# cigar_mic.net
KiCad netlist of a schematic drawn in EAGLE
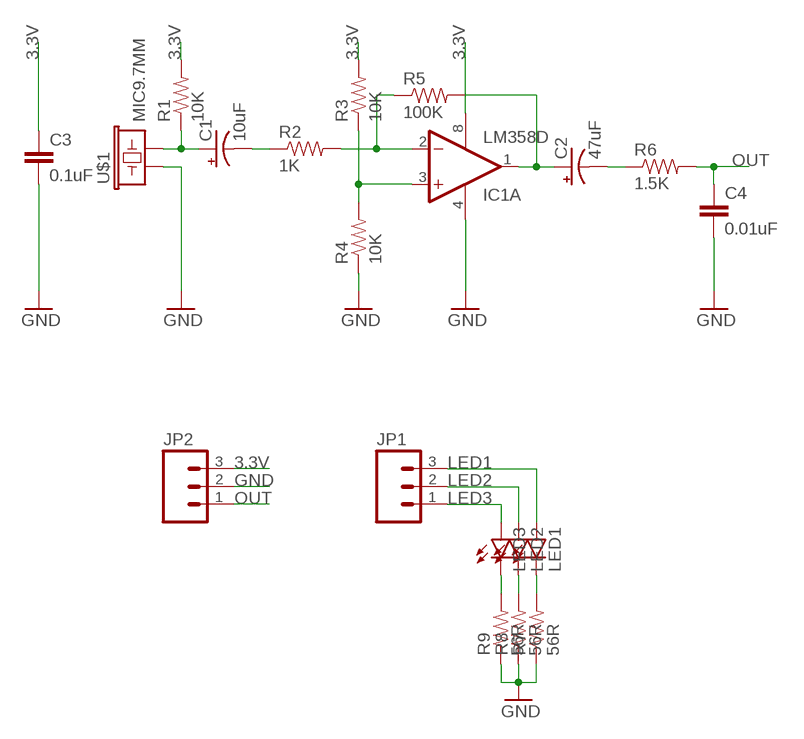
[diagram p0: schematic, sheet 1]

(export (version "E")
  (design (tool "Eeschema 10.0.6"))
  (components
    (comp (ref "C1")
      (value "10uF")
      (footprint "eagle-import:POLAR")
      (libsource (lib "eagle-import") (part "SURFACEMTPOLAR"))
    )
    (comp (ref "C2")
      (value "47uF")
      (footprint "eagle-import:POLAR")
      (libsource (lib "eagle-import") (part "SURFACEMTPOLAR"))
    )
    (comp (ref "C3")
      (value "0.1uF")
      (footprint "eagle-import:0805")
      (libsource (lib "eagle-import") (part "CAP0805"))
    )
    (comp (ref "C4")
      (value "0.01uF")
      (footprint "eagle-import:0805")
      (libsource (lib "eagle-import") (part "CAP0805"))
    )
    (comp (ref "IC1")
      (value "LM358D")
      (footprint "eagle-import:SO08")
      (libsource (lib "eagle-import") (part "LM358D"))
    )
    (comp (ref "JP1")
      (value "M031X03_NO_SILK")
      (footprint "eagle-import:1X03_NO_SILK")
      (libsource (lib "eagle-import") (part "M031X03_NO_SILK"))
    )
    (comp (ref "JP2")
      (value "M031X03_NO_SILK")
      (footprint "eagle-import:1X03_NO_SILK")
      (libsource (lib "eagle-import") (part "M031X03_NO_SILK"))
    )
    (comp (ref "LED1")
      (value "LED0603")
      (footprint "eagle-import:LED-0603")
      (libsource (lib "eagle-import") (part "LED0603"))
    )
    (comp (ref "LED2")
      (value "LED0603")
      (footprint "eagle-import:LED-0603")
      (libsource (lib "eagle-import") (part "LED0603"))
    )
    (comp (ref "LED3")
      (value "LED0603")
      (footprint "eagle-import:LED-0603")
      (libsource (lib "eagle-import") (part "LED0603"))
    )
    (comp (ref "R1")
      (value "10K")
      (footprint "eagle-import:0603-RES")
      (libsource (lib "eagle-import") (part "RESISTOR0603"))
    )
    (comp (ref "R2")
      (value "1K")
      (footprint "eagle-import:0603-RES")
      (libsource (lib "eagle-import") (part "RESISTOR0603"))
    )
    (comp (ref "R3")
      (value "10K")
      (footprint "eagle-import:0603-RES")
      (libsource (lib "eagle-import") (part "RESISTOR0603"))
    )
    (comp (ref "R4")
      (value "10K")
      (footprint "eagle-import:0603-RES")
      (libsource (lib "eagle-import") (part "RESISTOR0603"))
    )
    (comp (ref "R5")
      (value "100K")
      (footprint "eagle-import:0603-RES")
      (libsource (lib "eagle-import") (part "RESISTOR0603"))
    )
    (comp (ref "R6")
      (value "1.5K")
      (footprint "eagle-import:0603-RES")
      (libsource (lib "eagle-import") (part "RESISTOR0603"))
    )
    (comp (ref "R7")
      (value "56R")
      (footprint "eagle-import:0603-RES")
      (libsource (lib "eagle-import") (part "RESISTOR0603"))
    )
    (comp (ref "R8")
      (value "56R")
      (footprint "eagle-import:0603-RES")
      (libsource (lib "eagle-import") (part "RESISTOR0603"))
    )
    (comp (ref "R9")
      (value "56R")
      (footprint "eagle-import:0603-RES")
      (libsource (lib "eagle-import") (part "RESISTOR0603"))
    )
    (comp (ref "U$1")
      (value "MIC9.7MM")
      (footprint "eagle-import:MIC-9.7MM")
      (libsource (lib "eagle-import") (part "MIC9.7MM"))
    )
  )
  (nets
    (net (code "1") (name "/3.3V") (class "Default")
      (node (ref "C3") (pin "1") (pinfunction "1_1") (pintype "passive"))
      (node (ref "IC1") (pin "8") (pinfunction "V+_8") (pintype "power_in"))
      (node (ref "JP2") (pin "3") (pinfunction "3_3") (pintype "passive"))
      (node (ref "R1") (pin "2") (pinfunction "2_2") (pintype "passive"))
      (node (ref "R3") (pin "2") (pinfunction "2_2") (pintype "passive"))
    )
    (net (code "2") (name "/LED1") (class "Default")
      (node (ref "JP1") (pin "3") (pinfunction "3_3") (pintype "passive"))
      (node (ref "LED1") (pin "A") (pinfunction "A_A") (pintype "passive"))
    )
    (net (code "3") (name "/LED2") (class "Default")
      (node (ref "JP1") (pin "2") (pinfunction "2_2") (pintype "passive"))
      (node (ref "LED2") (pin "A") (pinfunction "A_A") (pintype "passive"))
    )
    (net (code "4") (name "/LED3") (class "Default")
      (node (ref "JP1") (pin "1") (pinfunction "1_1") (pintype "passive"))
      (node (ref "LED3") (pin "A") (pinfunction "A_A") (pintype "passive"))
    )
    (net (code "5") (name "/OUT") (class "Default")
      (node (ref "C4") (pin "1") (pinfunction "1_1") (pintype "passive"))
      (node (ref "JP2") (pin "1") (pinfunction "1_1") (pintype "passive"))
      (node (ref "R6") (pin "2") (pinfunction "2_2") (pintype "passive"))
    )
    (net (code "6") (name "GND") (class "Default")
      (node (ref "C3") (pin "2") (pinfunction "2_2") (pintype "passive"))
      (node (ref "C4") (pin "2") (pinfunction "2_2") (pintype "passive"))
      (node (ref "IC1") (pin "4") (pinfunction "V-_4") (pintype "power_in"))
      (node (ref "JP2") (pin "2") (pinfunction "2_2") (pintype "passive"))
      (node (ref "R4") (pin "1") (pinfunction "1_1") (pintype "passive"))
      (node (ref "R7") (pin "1") (pinfunction "1_1") (pintype "passive"))
      (node (ref "R8") (pin "1") (pinfunction "1_1") (pintype "passive"))
      (node (ref "R9") (pin "1") (pinfunction "1_1") (pintype "passive"))
      (node (ref "U$1") (pin "1") (pinfunction "1_1") (pintype "passive"))
    )
    (net (code "7") (name "Net-(C1-+)") (class "Default")
      (node (ref "C1") (pin "P$1") (pinfunction "+_P$1") (pintype "passive"))
      (node (ref "R1") (pin "1") (pinfunction "1_1") (pintype "passive"))
      (node (ref "U$1") (pin "2") (pinfunction "2_2") (pintype "passive"))
    )
    (net (code "8") (name "Net-(C1--)") (class "Default")
      (node (ref "C1") (pin "P$2") (pinfunction "-_P$2") (pintype "passive"))
      (node (ref "R2") (pin "1") (pinfunction "1_1") (pintype "passive"))
    )
    (net (code "9") (name "Net-(C2-+)") (class "Default")
      (node (ref "C2") (pin "P$1") (pinfunction "+_P$1") (pintype "passive"))
      (node (ref "IC1") (pin "1") (pinfunction "OUT_1") (pintype "output"))
      (node (ref "R5") (pin "2") (pinfunction "2_2") (pintype "passive"))
    )
    (net (code "10") (name "Net-(C2--)") (class "Default")
      (node (ref "C2") (pin "P$2") (pinfunction "-_P$2") (pintype "passive"))
      (node (ref "R6") (pin "1") (pinfunction "1_1") (pintype "passive"))
    )
    (net (code "11") (name "Net-(IC1A-+IN)") (class "Default")
      (node (ref "IC1") (pin "3") (pinfunction "+IN_3") (pintype "input"))
      (node (ref "R3") (pin "1") (pinfunction "1_1") (pintype "passive"))
      (node (ref "R4") (pin "2") (pinfunction "2_2") (pintype "passive"))
    )
    (net (code "12") (name "Net-(IC1A--IN)") (class "Default")
      (node (ref "IC1") (pin "2") (pinfunction "-IN_2") (pintype "input"))
      (node (ref "R2") (pin "2") (pinfunction "2_2") (pintype "passive"))
      (node (ref "R5") (pin "1") (pinfunction "1_1") (pintype "passive"))
    )
    (net (code "13") (name "Net-(LED1-PadC)") (class "Default")
      (node (ref "LED1") (pin "C") (pinfunction "C_C") (pintype "passive"))
      (node (ref "R7") (pin "2") (pinfunction "2_2") (pintype "passive"))
    )
    (net (code "14") (name "Net-(LED2-PadC)") (class "Default")
      (node (ref "LED2") (pin "C") (pinfunction "C_C") (pintype "passive"))
      (node (ref "R8") (pin "2") (pinfunction "2_2") (pintype "passive"))
    )
    (net (code "15") (name "Net-(LED3-PadC)") (class "Default")
      (node (ref "LED3") (pin "C") (pinfunction "C_C") (pintype "passive"))
      (node (ref "R9") (pin "2") (pinfunction "2_2") (pintype "passive"))
    )
  )
)
